# controller.net
KiCad netlist of a schematic drawn in EAGLE
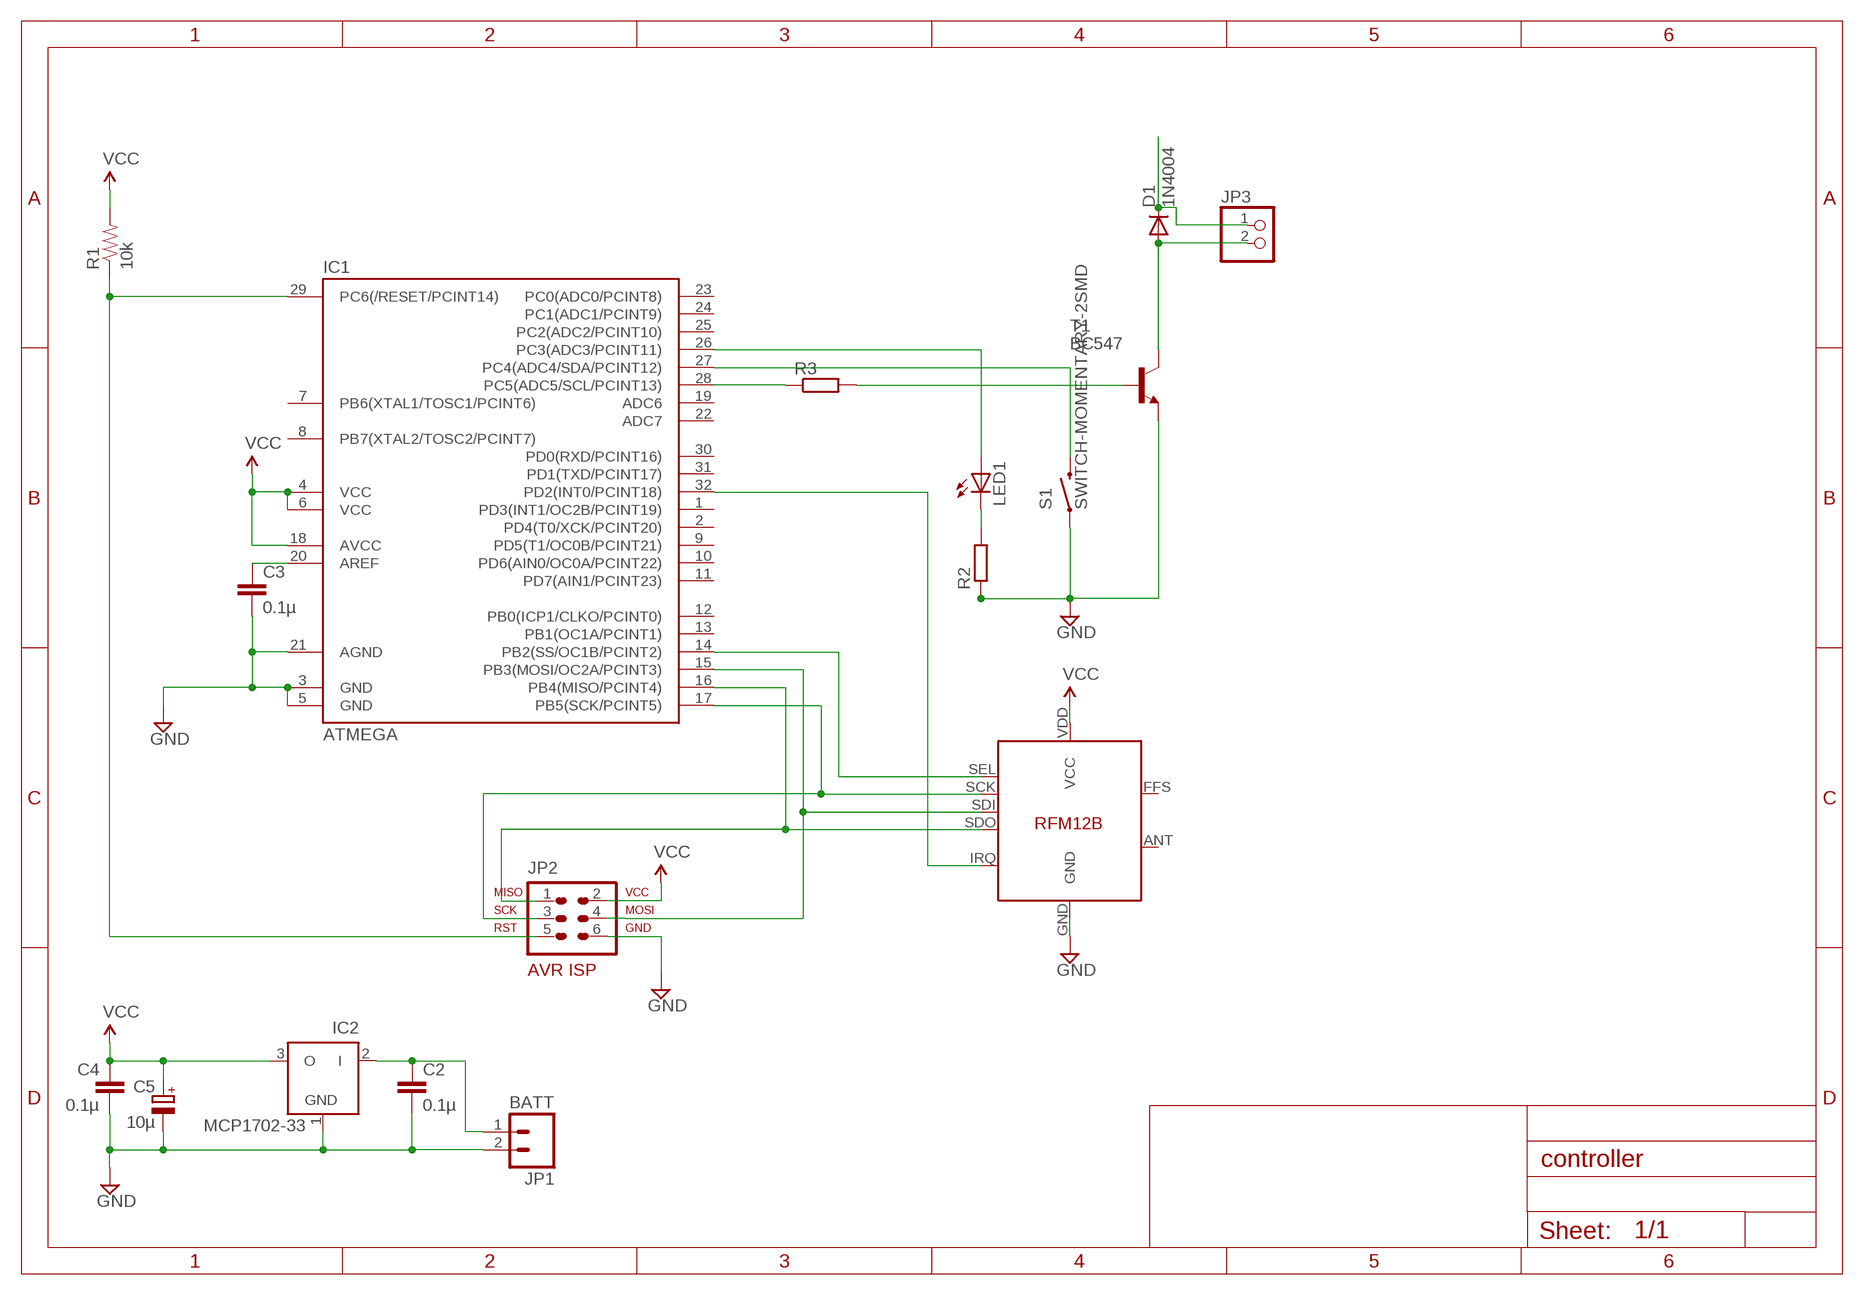
[diagram p0: schematic, sheet 1]

(export (version "E")
  (design (tool "Eeschema 10.0.6"))
  (components
    (comp (ref "C2")
      (value "0.1µ")
      (footprint "eagle-import:0805")
      (libsource (lib "eagle-import") (part "CAP0805"))
    )
    (comp (ref "C3")
      (value "0.1µ")
      (footprint "eagle-import:0805")
      (libsource (lib "eagle-import") (part "CAP0805"))
    )
    (comp (ref "C4")
      (value "0.1µ")
      (footprint "eagle-import:0805")
      (libsource (lib "eagle-import") (part "CAP0805"))
    )
    (comp (ref "C5")
      (value "10µ")
      (footprint "eagle-import:E1,8-4")
      (libsource (lib "eagle-import") (part "CPOL-EUE1.8-4"))
    )
    (comp (ref "D1")
      (value "1N4004")
      (footprint "eagle-import:DO41-10")
      (libsource (lib "eagle-import") (part "1N4004"))
    )
    (comp (ref "IC1")
      (value "ATMEGA")
      (footprint "eagle-import:TQFP32-08")
      (libsource (lib "eagle-import") (part "MEGA48/88/168-AU"))
    )
    (comp (ref "IC2")
      (value "MCP1702-33")
      (footprint "eagle-import:TO92")
      (libsource (lib "eagle-import") (part "MCP1702Z"))
    )
    (comp (ref "JP1")
      (value "BATT")
      (footprint "eagle-import:1X02_LOCK_LONGPADS")
      (libsource (lib "eagle-import") (part "M02LOCK_LONGPADS"))
    )
    (comp (ref "JP2")
      (value "AVR-ISP-6VERT")
      (footprint "eagle-import:AVR-ISP-6")
      (libsource (lib "eagle-import") (part "AVR-ISP-6VERT"))
    )
    (comp (ref "JP3")
      (value "PINHD-1X2")
      (footprint "eagle-import:1X02")
      (libsource (lib "eagle-import") (part "PINHD-1X2"))
    )
    (comp (ref "LED1")
      (value "LEDCHIPLED_0805")
      (footprint "eagle-import:CHIPLED_0805")
      (libsource (lib "eagle-import") (part "LEDCHIPLED_0805"))
    )
    (comp (ref "R1")
      (value "10k")
      (footprint "eagle-import:0805")
      (libsource (lib "eagle-import") (part "RESISTOR0805-RES"))
    )
    (comp (ref "R2")
      (value "R-EU_0207/10")
      (footprint "eagle-import:0207_10")
      (libsource (lib "eagle-import") (part "R-EU_0207/10"))
    )
    (comp (ref "R3")
      (value "R-EU_0207/10")
      (footprint "eagle-import:0207_10")
      (libsource (lib "eagle-import") (part "R-EU_0207/10"))
    )
    (comp (ref "S1")
      (value "SWITCH-MOMENTARY-2SMD")
      (footprint "eagle-import:TACTILE_SWITCH_SMD")
      (libsource (lib "eagle-import") (part "SWITCH-MOMENTARY-2SMD"))
    )
    (comp (ref "T1")
      (value "BC547")
      (footprint "eagle-import:TO92")
      (libsource (lib "eagle-import") (part "BC547"))
    )
    (comp (ref "U$1")
      (value "RFM12B")
      (footprint "eagle-import:RFM12B")
      (libsource (lib "eagle-import") (part "RFM12B"))
    )
  )
  (nets
    (net (code "1") (name "/PWR") (class "Default")
      (node (ref "C2") (pin "1") (pinfunction "1_1") (pintype "passive"))
      (node (ref "D1") (pin "C") (pinfunction "C_C") (pintype "passive"))
      (node (ref "IC2") (pin "2") (pinfunction "I_2") (pintype "input"))
      (node (ref "JP1") (pin "1") (pinfunction "1_1") (pintype "passive"))
      (node (ref "JP3") (pin "1") (pinfunction "1_1") (pintype "passive"))
    )
    (net (code "2") (name "GND") (class "Default")
      (node (ref "C2") (pin "2") (pinfunction "2_2") (pintype "passive"))
      (node (ref "C3") (pin "2") (pinfunction "2_2") (pintype "passive"))
      (node (ref "C4") (pin "2") (pinfunction "2_2") (pintype "passive"))
      (node (ref "C5") (pin "-") (pinfunction "-_-") (pintype "passive"))
      (node (ref "IC1") (pin "21") (pinfunction "AGND_21") (pintype "power_in"))
      (node (ref "IC1") (pin "3") (pinfunction "GND_3") (pintype "power_in"))
      (node (ref "IC1") (pin "5") (pinfunction "GND_5") (pintype "power_in"))
      (node (ref "IC2") (pin "1") (pinfunction "GND_1") (pintype "power_in"))
      (node (ref "JP1") (pin "2") (pinfunction "2_2") (pintype "passive"))
      (node (ref "JP2") (pin "6") (pinfunction "6_6") (pintype "passive"))
      (node (ref "R2") (pin "1") (pinfunction "1_1") (pintype "passive"))
      (node (ref "S1") (pin "1") (pinfunction "1_1") (pintype "passive"))
      (node (ref "T1") (pin "1") (pinfunction "E_1") (pintype "passive"))
      (node (ref "U$1") (pin "GND") (pinfunction "GND_GND") (pintype "power_in"))
    )
    (net (code "3") (name "Net-(IC1-AREF)") (class "Default")
      (node (ref "C3") (pin "1") (pinfunction "1_1") (pintype "passive"))
      (node (ref "IC1") (pin "20") (pinfunction "AREF_20") (pintype "passive"))
    )
    (net (code "4") (name "Net-(IC1-PB2(SS{slash}OC1B{slash}PCINT2))") (class "Default")
      (node (ref "IC1") (pin "14") (pinfunction "PB2(SS/OC1B/PCINT2)_14") (pintype "bidirectional"))
      (node (ref "U$1") (pin "SEL") (pinfunction "SEL_SEL") (pintype "input"))
    )
    (net (code "5") (name "Net-(IC1-PB3(MOSI{slash}OC2A{slash}PCINT3))") (class "Default")
      (node (ref "IC1") (pin "15") (pinfunction "PB3(MOSI/OC2A/PCINT3)_15") (pintype "bidirectional"))
      (node (ref "JP2") (pin "4") (pinfunction "4_4") (pintype "passive"))
      (node (ref "U$1") (pin "SDI") (pinfunction "SDI_SDI") (pintype "input"))
    )
    (net (code "6") (name "Net-(IC1-PB4(MISO{slash}PCINT4))") (class "Default")
      (node (ref "IC1") (pin "16") (pinfunction "PB4(MISO/PCINT4)_16") (pintype "bidirectional"))
      (node (ref "JP2") (pin "1") (pinfunction "1_1") (pintype "passive"))
      (node (ref "U$1") (pin "SDO") (pinfunction "SDO_SDO") (pintype "output"))
    )
    (net (code "7") (name "Net-(IC1-PB5(SCK{slash}PCINT5))") (class "Default")
      (node (ref "IC1") (pin "17") (pinfunction "PB5(SCK/PCINT5)_17") (pintype "bidirectional"))
      (node (ref "JP2") (pin "3") (pinfunction "3_3") (pintype "passive"))
      (node (ref "U$1") (pin "SCK") (pinfunction "SCK_SCK") (pintype "input"))
    )
    (net (code "8") (name "Net-(IC1-PC3(ADC3{slash}PCINT11))") (class "Default")
      (node (ref "IC1") (pin "26") (pinfunction "PC3(ADC3/PCINT11)_26") (pintype "bidirectional"))
      (node (ref "LED1") (pin "A") (pinfunction "A_A") (pintype "passive"))
    )
    (net (code "9") (name "Net-(IC1-PC4(ADC4{slash}SDA{slash}PCINT12))") (class "Default")
      (node (ref "IC1") (pin "27") (pinfunction "PC4(ADC4/SDA/PCINT12)_27") (pintype "bidirectional"))
      (node (ref "S1") (pin "3") (pinfunction "2_3") (pintype "passive"))
    )
    (net (code "10") (name "Net-(IC1-PC5(ADC5{slash}SCL{slash}PCINT13))") (class "Default")
      (node (ref "IC1") (pin "28") (pinfunction "PC5(ADC5/SCL/PCINT13)_28") (pintype "bidirectional"))
      (node (ref "R3") (pin "1") (pinfunction "1_1") (pintype "passive"))
    )
    (net (code "11") (name "Net-(IC1-PC6({slash}RESET{slash}PCINT14))") (class "Default")
      (node (ref "IC1") (pin "29") (pinfunction "PC6(/RESET/PCINT14)_29") (pintype "bidirectional"))
      (node (ref "JP2") (pin "5") (pinfunction "5_5") (pintype "passive"))
      (node (ref "R1") (pin "1") (pinfunction "1_1") (pintype "passive"))
    )
    (net (code "12") (name "Net-(IC1-PD2(INT0{slash}PCINT18))") (class "Default")
      (node (ref "IC1") (pin "32") (pinfunction "PD2(INT0/PCINT18)_32") (pintype "bidirectional"))
      (node (ref "U$1") (pin "IRQ") (pinfunction "IRQ_IRQ") (pintype "open_collector"))
    )
    (net (code "13") (name "Net-(LED1-PadC)") (class "Default")
      (node (ref "LED1") (pin "C") (pinfunction "C_C") (pintype "passive"))
      (node (ref "R2") (pin "2") (pinfunction "2_2") (pintype "passive"))
    )
    (net (code "14") (name "Net-(T1-B)") (class "Default")
      (node (ref "R3") (pin "2") (pinfunction "2_2") (pintype "passive"))
      (node (ref "T1") (pin "2") (pinfunction "B_2") (pintype "passive"))
    )
    (net (code "15") (name "Net-(T1-C)") (class "Default")
      (node (ref "D1") (pin "A") (pinfunction "A_A") (pintype "passive"))
      (node (ref "JP3") (pin "2") (pinfunction "2_2") (pintype "passive"))
      (node (ref "T1") (pin "3") (pinfunction "C_3") (pintype "passive"))
    )
    (net (code "16") (name "VCC") (class "Default")
      (node (ref "C4") (pin "1") (pinfunction "1_1") (pintype "passive"))
      (node (ref "C5") (pin "+") (pinfunction "+_+") (pintype "passive"))
      (node (ref "IC1") (pin "18") (pinfunction "AVCC_18") (pintype "passive"))
      (node (ref "IC1") (pin "4") (pinfunction "VCC_4") (pintype "power_in"))
      (node (ref "IC1") (pin "6") (pinfunction "VCC_6") (pintype "power_in"))
      (node (ref "IC2") (pin "3") (pinfunction "O_3") (pintype "input"))
      (node (ref "JP2") (pin "2") (pinfunction "2_2") (pintype "passive"))
      (node (ref "R1") (pin "2") (pinfunction "2_2") (pintype "passive"))
      (node (ref "U$1") (pin "VDD") (pinfunction "VCC_VDD") (pintype "power_in"))
    )
    (net (code "17") (name "unconnected-(IC1-ADC6-Pad19)") (class "Default")
      (node (ref "IC1") (pin "19") (pinfunction "ADC6_19") (pintype "passive"))
    )
    (net (code "18") (name "unconnected-(IC1-ADC7-Pad22)") (class "Default")
      (node (ref "IC1") (pin "22") (pinfunction "ADC7_22") (pintype "passive"))
    )
    (net (code "19") (name "unconnected-(IC1-PB0(ICP1{slash}CLKO{slash}PCINT0)-Pad12)") (class "Default")
      (node (ref "IC1") (pin "12") (pinfunction "PB0(ICP1/CLKO/PCINT0)_12") (pintype "bidirectional"))
    )
    (net (code "20") (name "unconnected-(IC1-PB1(OC1A{slash}PCINT1)-Pad13)") (class "Default")
      (node (ref "IC1") (pin "13") (pinfunction "PB1(OC1A/PCINT1)_13") (pintype "bidirectional"))
    )
    (net (code "21") (name "unconnected-(IC1-PB6(XTAL1{slash}TOSC1{slash}PCINT6)-Pad7)") (class "Default")
      (node (ref "IC1") (pin "7") (pinfunction "PB6(XTAL1/TOSC1/PCINT6)_7") (pintype "bidirectional"))
    )
    (net (code "22") (name "unconnected-(IC1-PB7(XTAL2{slash}TOSC2{slash}PCINT7)-Pad8)") (class "Default")
      (node (ref "IC1") (pin "8") (pinfunction "PB7(XTAL2/TOSC2/PCINT7)_8") (pintype "bidirectional"))
    )
    (net (code "23") (name "unconnected-(IC1-PC0(ADC0{slash}PCINT8)-Pad23)") (class "Default")
      (node (ref "IC1") (pin "23") (pinfunction "PC0(ADC0/PCINT8)_23") (pintype "bidirectional"))
    )
    (net (code "24") (name "unconnected-(IC1-PC1(ADC1{slash}PCINT9)-Pad24)") (class "Default")
      (node (ref "IC1") (pin "24") (pinfunction "PC1(ADC1/PCINT9)_24") (pintype "bidirectional"))
    )
    (net (code "25") (name "unconnected-(IC1-PC2(ADC2{slash}PCINT10)-Pad25)") (class "Default")
      (node (ref "IC1") (pin "25") (pinfunction "PC2(ADC2/PCINT10)_25") (pintype "bidirectional"))
    )
    (net (code "26") (name "unconnected-(IC1-PD0(RXD{slash}PCINT16)-Pad30)") (class "Default")
      (node (ref "IC1") (pin "30") (pinfunction "PD0(RXD/PCINT16)_30") (pintype "bidirectional"))
    )
    (net (code "27") (name "unconnected-(IC1-PD1(TXD{slash}PCINT17)-Pad31)") (class "Default")
      (node (ref "IC1") (pin "31") (pinfunction "PD1(TXD/PCINT17)_31") (pintype "bidirectional"))
    )
    (net (code "28") (name "unconnected-(IC1-PD3(INT1{slash}OC2B{slash}PCINT19)-Pad1)") (class "Default")
      (node (ref "IC1") (pin "1") (pinfunction "PD3(INT1/OC2B/PCINT19)_1") (pintype "bidirectional"))
    )
    (net (code "29") (name "unconnected-(IC1-PD4(T0{slash}XCK{slash}PCINT20)-Pad2)") (class "Default")
      (node (ref "IC1") (pin "2") (pinfunction "PD4(T0/XCK/PCINT20)_2") (pintype "bidirectional"))
    )
    (net (code "30") (name "unconnected-(IC1-PD5(T1{slash}OC0B{slash}PCINT21)-Pad9)") (class "Default")
      (node (ref "IC1") (pin "9") (pinfunction "PD5(T1/OC0B/PCINT21)_9") (pintype "bidirectional"))
    )
    (net (code "31") (name "unconnected-(IC1-PD6(AIN0{slash}OC0A{slash}PCINT22)-Pad10)") (class "Default")
      (node (ref "IC1") (pin "10") (pinfunction "PD6(AIN0/OC0A/PCINT22)_10") (pintype "bidirectional"))
    )
    (net (code "32") (name "unconnected-(IC1-PD7(AIN1{slash}PCINT23)-Pad11)") (class "Default")
      (node (ref "IC1") (pin "11") (pinfunction "PD7(AIN1/PCINT23)_11") (pintype "bidirectional"))
    )
    (net (code "33") (name "unconnected-(U$1-PadANT)") (class "Default")
      (node (ref "U$1") (pin "ANT") (pinfunction "ANT_ANT") (pintype "passive"))
    )
    (net (code "34") (name "unconnected-(U$1-PadFFS)") (class "Default")
      (node (ref "U$1") (pin "FFS") (pinfunction "FFS_FFS") (pintype "bidirectional"))
    )
  )
)
